# ZipIT_rev1.net
KiCad netlist of a schematic drawn in EAGLE
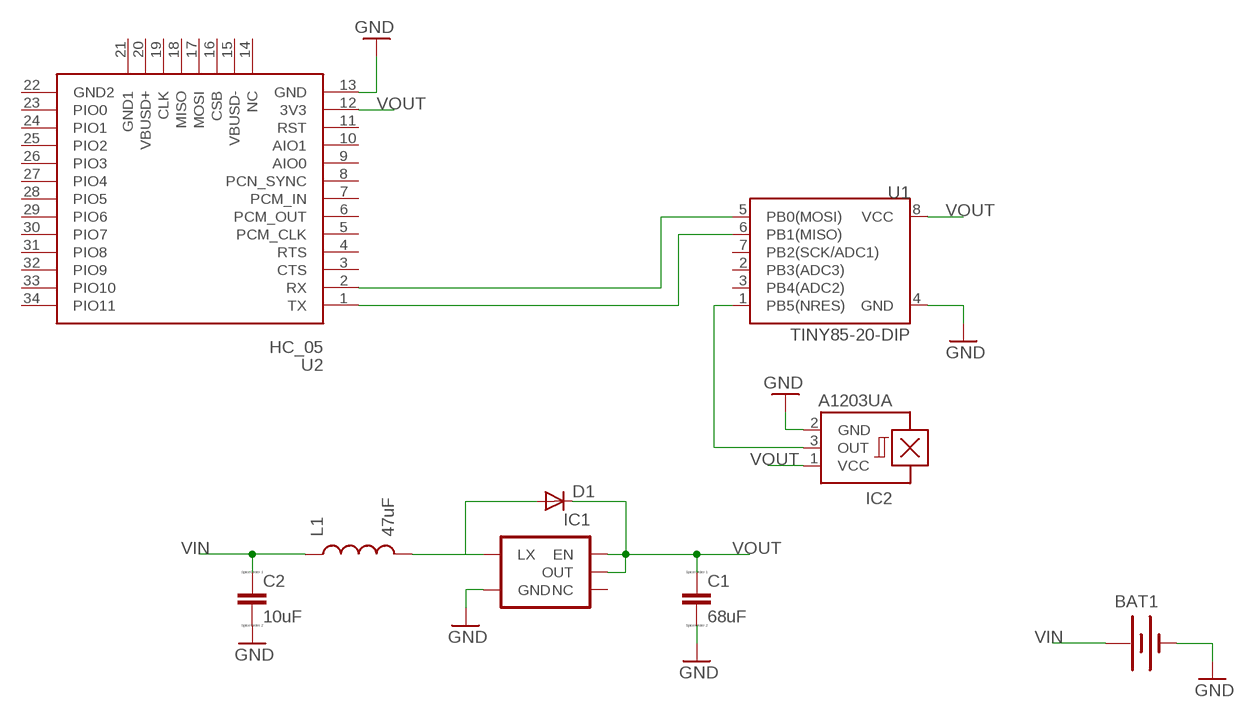
[diagram p0: schematic, sheet 1]

(export (version "E")
  (design (tool "Eeschema 10.0.6"))
  (components
    (comp (ref "BAT1")
      (value "BATTERYAAA")
      (footprint "eagle-import:BATTERY-AAA")
      (libsource (lib "eagle-import") (part "BATTERYAAA"))
    )
    (comp (ref "C1")
      (value "68uF")
      (footprint "eagle-import:C1210")
      (libsource (lib "eagle-import") (part "CC1210"))
    )
    (comp (ref "C2")
      (value "10uF")
      (footprint "eagle-import:C1206")
      (libsource (lib "eagle-import") (part "CC1206"))
    )
    (comp (ref "D1")
      (value "DIODE-DO214AC")
      (footprint "eagle-import:DO214AC")
      (libsource (lib "eagle-import") (part "DIODE-DO214AC"))
    )
    (comp (ref "IC1")
      (value "V_REG_NCP1400SOT23-5")
      (footprint "eagle-import:SOT23-5")
      (libsource (lib "eagle-import") (part "V_REG_NCP1400SOT23-5"))
    )
    (comp (ref "IC2")
      (value "A1203UA")
      (footprint "eagle-import:SIP3-UA")
      (libsource (lib "eagle-import") (part "A12?UA03"))
    )
    (comp (ref "L1")
      (value "47uF")
      (footprint "eagle-import:CR54")
      (libsource (lib "eagle-import") (part "INDUCTORCR54"))
    )
    (comp (ref "U1")
      (value "TINY85-20-DIP")
      (footprint "eagle-import:DIP08")
      (libsource (lib "eagle-import") (part "ATTINY45TINY85-20-DIP"))
    )
    (comp (ref "U2")
      (value "HC_05")
      (footprint "eagle-import:BLUETOOTH_SMD")
      (libsource (lib "eagle-import") (part "HC_05"))
    )
  )
  (nets
    (net (code "1") (name "/VIN") (class "Default")
      (node (ref "BAT1") (pin "PWR@1") (pinfunction "+_PWR@1") (pintype "power_in"))
      (node (ref "C2") (pin "1") (pinfunction "1_1") (pintype "passive"))
      (node (ref "L1") (pin "P$1") (pinfunction "1_P$1") (pintype "passive"))
    )
    (net (code "2") (name "/VOUT") (class "Default")
      (node (ref "C1") (pin "1") (pinfunction "1_1") (pintype "passive"))
      (node (ref "D1") (pin "C") (pinfunction "C_C") (pintype "passive"))
      (node (ref "IC1") (pin "1") (pinfunction "EN_1") (pintype "input"))
      (node (ref "IC1") (pin "2") (pinfunction "OUT_2") (pintype "passive"))
      (node (ref "IC2") (pin "1") (pinfunction "VCC_1") (pintype "power_in"))
      (node (ref "U1") (pin "8") (pinfunction "VCC_8") (pintype "bidirectional"))
      (node (ref "U2") (pin "12") (pinfunction "3V3_12") (pintype "bidirectional"))
    )
    (net (code "3") (name "GND") (class "Default")
      (node (ref "BAT1") (pin "GND@1") (pinfunction "-_GND@1") (pintype "power_in"))
      (node (ref "C1") (pin "2") (pinfunction "2_2") (pintype "passive"))
      (node (ref "C2") (pin "2") (pinfunction "2_2") (pintype "passive"))
      (node (ref "IC1") (pin "4") (pinfunction "GND_4") (pintype "input"))
      (node (ref "IC2") (pin "2") (pinfunction "GND_2") (pintype "power_in"))
      (node (ref "U1") (pin "4") (pinfunction "GND_4") (pintype "bidirectional"))
      (node (ref "U2") (pin "13") (pinfunction "GND_13") (pintype "bidirectional"))
    )
    (net (code "4") (name "Net-(IC1-LX)") (class "Default")
      (node (ref "D1") (pin "A") (pinfunction "A_A") (pintype "passive"))
      (node (ref "IC1") (pin "5") (pinfunction "LX_5") (pintype "input"))
      (node (ref "L1") (pin "P$2") (pinfunction "2_P$2") (pintype "passive"))
    )
    (net (code "5") (name "Net-(IC2-OUT)") (class "Default")
      (node (ref "IC2") (pin "3") (pinfunction "OUT_3") (pintype "output"))
      (node (ref "U1") (pin "1") (pinfunction "PB5(NRES)_1") (pintype "bidirectional"))
    )
    (net (code "6") (name "Net-(U1-PB0(MOSI))") (class "Default")
      (node (ref "U1") (pin "5") (pinfunction "PB0(MOSI)_5") (pintype "bidirectional"))
      (node (ref "U2") (pin "2") (pinfunction "RX_2") (pintype "bidirectional"))
    )
    (net (code "7") (name "Net-(U1-PB1(MISO))") (class "Default")
      (node (ref "U1") (pin "6") (pinfunction "PB1(MISO)_6") (pintype "bidirectional"))
      (node (ref "U2") (pin "1") (pinfunction "TX_1") (pintype "bidirectional"))
    )
    (net (code "8") (name "unconnected-(IC1-NC-Pad3)") (class "Default")
      (node (ref "IC1") (pin "3") (pinfunction "NC_3") (pintype "input"))
    )
    (net (code "9") (name "unconnected-(U1-PB2(SCK{slash}ADC1)-Pad7)") (class "Default")
      (node (ref "U1") (pin "7") (pinfunction "PB2(SCK/ADC1)_7") (pintype "bidirectional"))
    )
    (net (code "10") (name "unconnected-(U1-PB3(ADC3)-Pad2)") (class "Default")
      (node (ref "U1") (pin "2") (pinfunction "PB3(ADC3)_2") (pintype "bidirectional"))
    )
    (net (code "11") (name "unconnected-(U1-PB4(ADC2)-Pad3)") (class "Default")
      (node (ref "U1") (pin "3") (pinfunction "PB4(ADC2)_3") (pintype "bidirectional"))
    )
    (net (code "12") (name "unconnected-(U2-AIO0-Pad9)") (class "Default")
      (node (ref "U2") (pin "9") (pinfunction "AIO0_9") (pintype "bidirectional"))
    )
    (net (code "13") (name "unconnected-(U2-AIO1-Pad10)") (class "Default")
      (node (ref "U2") (pin "10") (pinfunction "AIO1_10") (pintype "bidirectional"))
    )
    (net (code "14") (name "unconnected-(U2-CLK-Pad19)") (class "Default")
      (node (ref "U2") (pin "19") (pinfunction "CLK_19") (pintype "bidirectional"))
    )
    (net (code "15") (name "unconnected-(U2-CSB-Pad16)") (class "Default")
      (node (ref "U2") (pin "16") (pinfunction "CSB_16") (pintype "bidirectional"))
    )
    (net (code "16") (name "unconnected-(U2-CTS-Pad3)") (class "Default")
      (node (ref "U2") (pin "3") (pinfunction "CTS_3") (pintype "bidirectional"))
    )
    (net (code "17") (name "unconnected-(U2-GND1-Pad21)") (class "Default")
      (node (ref "U2") (pin "21") (pinfunction "GND1_21") (pintype "bidirectional"))
    )
    (net (code "18") (name "unconnected-(U2-GND2-Pad22)") (class "Default")
      (node (ref "U2") (pin "22") (pinfunction "GND2_22") (pintype "bidirectional"))
    )
    (net (code "19") (name "unconnected-(U2-MISO-Pad18)") (class "Default")
      (node (ref "U2") (pin "18") (pinfunction "MISO_18") (pintype "bidirectional"))
    )
    (net (code "20") (name "unconnected-(U2-MOSI-Pad17)") (class "Default")
      (node (ref "U2") (pin "17") (pinfunction "MOSI_17") (pintype "bidirectional"))
    )
    (net (code "21") (name "unconnected-(U2-NC-Pad14)") (class "Default")
      (node (ref "U2") (pin "14") (pinfunction "NC_14") (pintype "bidirectional"))
    )
    (net (code "22") (name "unconnected-(U2-PCM_CLK-Pad5)") (class "Default")
      (node (ref "U2") (pin "5") (pinfunction "PCM_CLK_5") (pintype "bidirectional"))
    )
    (net (code "23") (name "unconnected-(U2-PCM_IN-Pad7)") (class "Default")
      (node (ref "U2") (pin "7") (pinfunction "PCM_IN_7") (pintype "bidirectional"))
    )
    (net (code "24") (name "unconnected-(U2-PCM_OUT-Pad6)") (class "Default")
      (node (ref "U2") (pin "6") (pinfunction "PCM_OUT_6") (pintype "bidirectional"))
    )
    (net (code "25") (name "unconnected-(U2-PCN_SYNC-Pad8)") (class "Default")
      (node (ref "U2") (pin "8") (pinfunction "PCN_SYNC_8") (pintype "bidirectional"))
    )
    (net (code "26") (name "unconnected-(U2-PIO0-Pad23)") (class "Default")
      (node (ref "U2") (pin "23") (pinfunction "PIO0_23") (pintype "bidirectional"))
    )
    (net (code "27") (name "unconnected-(U2-PIO1-Pad24)") (class "Default")
      (node (ref "U2") (pin "24") (pinfunction "PIO1_24") (pintype "bidirectional"))
    )
    (net (code "28") (name "unconnected-(U2-PIO2-Pad25)") (class "Default")
      (node (ref "U2") (pin "25") (pinfunction "PIO2_25") (pintype "bidirectional"))
    )
    (net (code "29") (name "unconnected-(U2-PIO3-Pad26)") (class "Default")
      (node (ref "U2") (pin "26") (pinfunction "PIO3_26") (pintype "bidirectional"))
    )
    (net (code "30") (name "unconnected-(U2-PIO4-Pad27)") (class "Default")
      (node (ref "U2") (pin "27") (pinfunction "PIO4_27") (pintype "bidirectional"))
    )
    (net (code "31") (name "unconnected-(U2-PIO5-Pad28)") (class "Default")
      (node (ref "U2") (pin "28") (pinfunction "PIO5_28") (pintype "bidirectional"))
    )
    (net (code "32") (name "unconnected-(U2-PIO6-Pad29)") (class "Default")
      (node (ref "U2") (pin "29") (pinfunction "PIO6_29") (pintype "bidirectional"))
    )
    (net (code "33") (name "unconnected-(U2-PIO7-Pad30)") (class "Default")
      (node (ref "U2") (pin "30") (pinfunction "PIO7_30") (pintype "bidirectional"))
    )
    (net (code "34") (name "unconnected-(U2-PIO8-Pad31)") (class "Default")
      (node (ref "U2") (pin "31") (pinfunction "PIO8_31") (pintype "bidirectional"))
    )
    (net (code "35") (name "unconnected-(U2-PIO9-Pad32)") (class "Default")
      (node (ref "U2") (pin "32") (pinfunction "PIO9_32") (pintype "bidirectional"))
    )
    (net (code "36") (name "unconnected-(U2-PIO10-Pad33)") (class "Default")
      (node (ref "U2") (pin "33") (pinfunction "PIO10_33") (pintype "bidirectional"))
    )
    (net (code "37") (name "unconnected-(U2-PIO11-Pad34)") (class "Default")
      (node (ref "U2") (pin "34") (pinfunction "PIO11_34") (pintype "bidirectional"))
    )
    (net (code "38") (name "unconnected-(U2-RST-Pad11)") (class "Default")
      (node (ref "U2") (pin "11") (pinfunction "RST_11") (pintype "bidirectional"))
    )
    (net (code "39") (name "unconnected-(U2-RTS-Pad4)") (class "Default")
      (node (ref "U2") (pin "4") (pinfunction "RTS_4") (pintype "bidirectional"))
    )
    (net (code "40") (name "unconnected-(U2-VBUSD+-Pad20)") (class "Default")
      (node (ref "U2") (pin "20") (pinfunction "VBUSD+_20") (pintype "bidirectional"))
    )
    (net (code "41") (name "unconnected-(U2-VBUSD--Pad15)") (class "Default")
      (node (ref "U2") (pin "15") (pinfunction "VBUSD-_15") (pintype "bidirectional"))
    )
  )
)
